# Camera_Control.net
KiCad netlist of a schematic drawn in Altium Designer
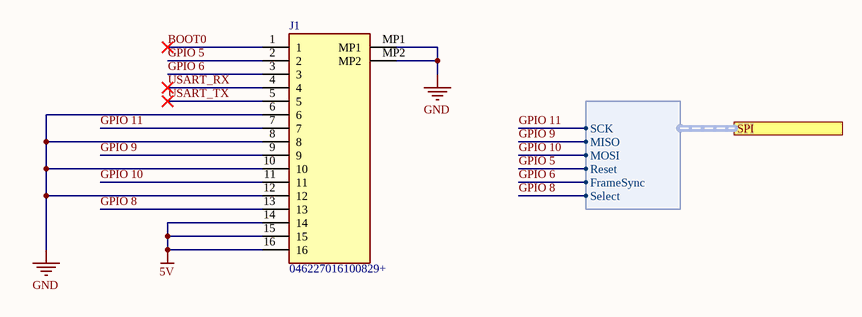
[diagram p0: Camera Control.SchDoc]

(export (version "E")
  (design (tool "Eeschema 10.0.6"))
  (components
    (comp (ref "J1")
      (value "046227016100829+")
      (footprint "SamacSys:046227016100800")
      (description "Connector")
      (fields
        (field (name "MANUFACTURER_PART_NUMBER") "046227016100800+")
        (field (name "MOUSER PART NUMBER") "581-046227016100800+")
      )
      (libsource (lib "*") (part "046227016100800+"))
    )
  )
  (nets
    (net (code "2") (name "/BOOT0") (class "Default")
      (node (ref "J1") (pin "1") (pinfunction "1_1") (pintype "passive+no_connect"))
    )
    (net (code "3") (name "/GPIO 5") (class "Default")
      (node (ref "J1") (pin "2") (pinfunction "2_2") (pintype "passive"))
    )
    (net (code "4") (name "/GPIO 6") (class "Default")
      (node (ref "J1") (pin "3") (pinfunction "3_3") (pintype "passive"))
    )
    (net (code "5") (name "/GPIO 8") (class "Default")
      (node (ref "J1") (pin "13") (pinfunction "13_13") (pintype "passive"))
    )
    (net (code "6") (name "/GPIO 9") (class "Default")
      (node (ref "J1") (pin "9") (pinfunction "9_9") (pintype "passive"))
    )
    (net (code "7") (name "/GPIO 10") (class "Default")
      (node (ref "J1") (pin "11") (pinfunction "11_11") (pintype "passive"))
    )
    (net (code "8") (name "/GPIO 11") (class "Default")
      (node (ref "J1") (pin "7") (pinfunction "7_7") (pintype "passive"))
    )
    (net (code "9") (name "/USART_RX") (class "Default")
      (node (ref "J1") (pin "4") (pinfunction "4_4") (pintype "passive+no_connect"))
    )
    (net (code "10") (name "/USART_TX") (class "Default")
      (node (ref "J1") (pin "5") (pinfunction "5_5") (pintype "passive+no_connect"))
    )
    (net (code "12") (name "5V") (class "Default")
      (node (ref "J1") (pin "14") (pinfunction "14_14") (pintype "passive"))
      (node (ref "J1") (pin "15") (pinfunction "15_15") (pintype "passive"))
      (node (ref "J1") (pin "16") (pinfunction "16_16") (pintype "passive"))
    )
    (net (code "13") (name "GND") (class "Default")
      (node (ref "J1") (pin "10") (pinfunction "10_10") (pintype "passive"))
      (node (ref "J1") (pin "12") (pinfunction "12_12") (pintype "passive"))
      (node (ref "J1") (pin "6") (pinfunction "6_6") (pintype "passive"))
      (node (ref "J1") (pin "8") (pinfunction "8_8") (pintype "passive"))
      (node (ref "J1") (pin "MP1") (pinfunction "MP1_MP1") (pintype "passive"))
      (node (ref "J1") (pin "MP2") (pinfunction "MP2_MP2") (pintype "passive"))
    )
  )
)
